# Camera_IR.net
KiCad netlist of a schematic drawn in EasyEDA
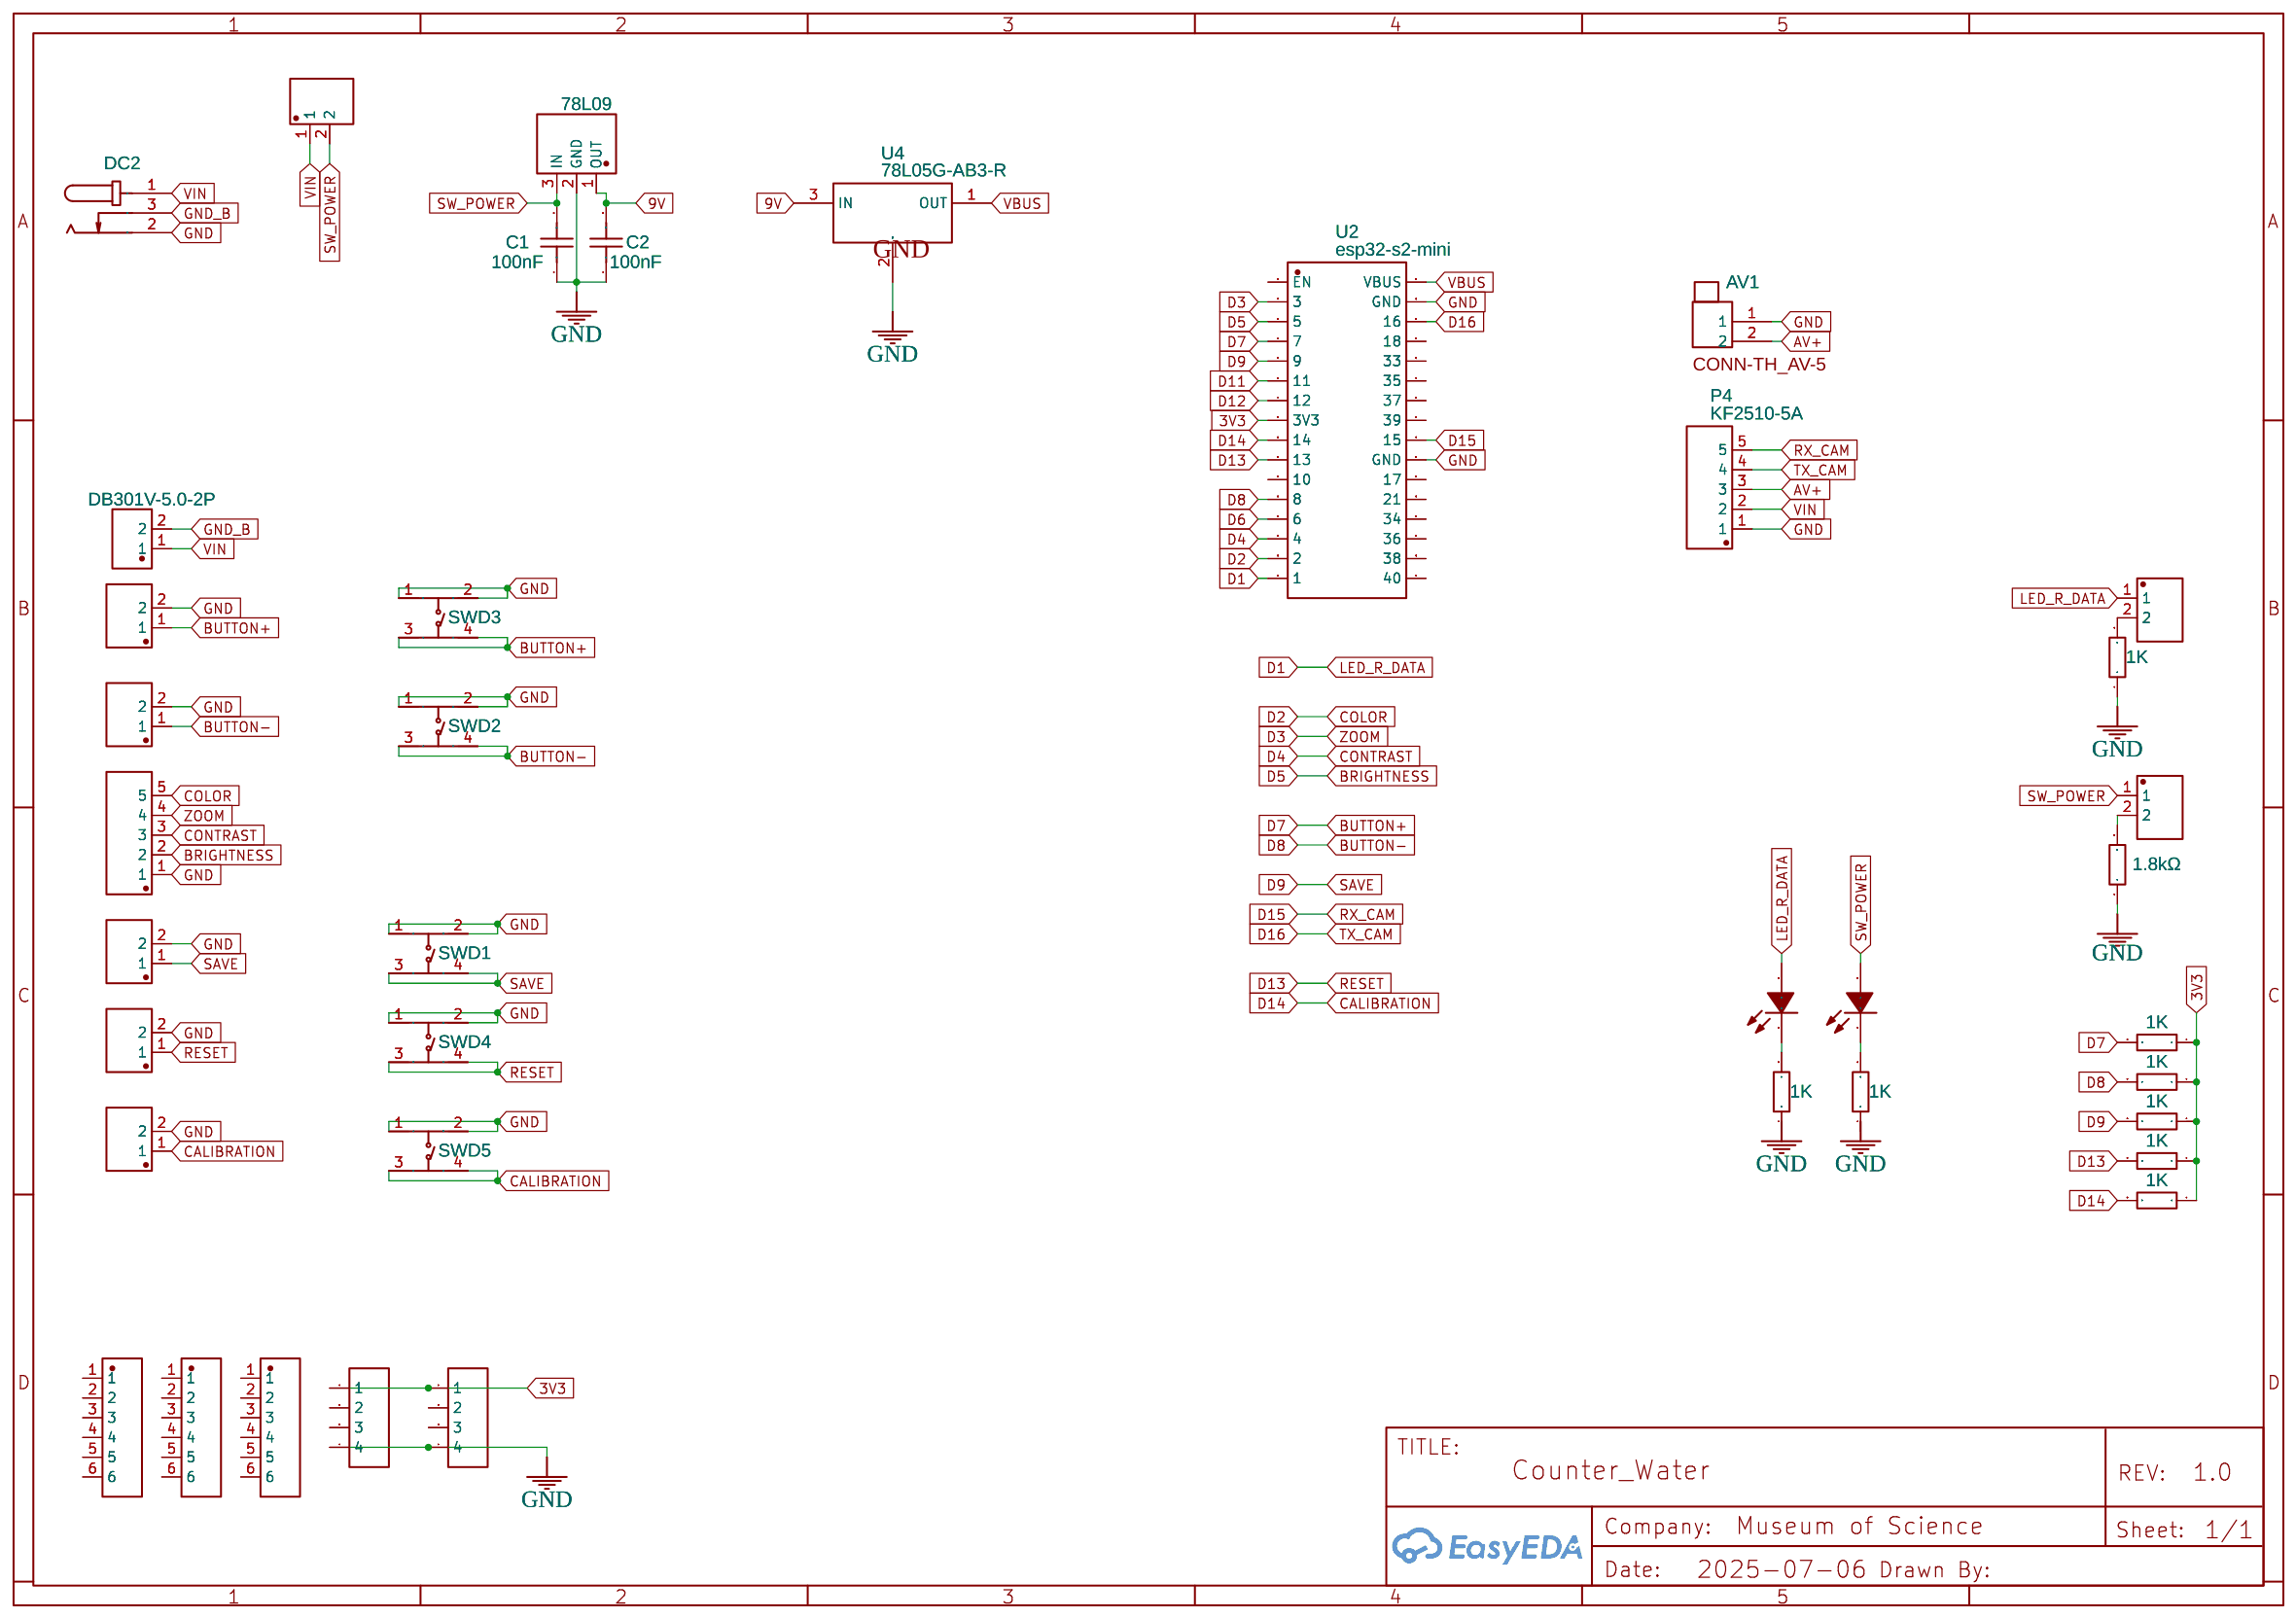
[diagram p0: schematic sheet]

(export (version "E")
  (design (tool "Eeschema 10.0.6"))
  (components
    (comp (ref "AV1")
      (value "AV-5")
      (fields (field (name "Manufacturer") "BOOMELE(博穆精密)"))
      (libsource (lib "") (part "AV-5"))
    )
    (comp (ref "C1")
      (value "100nF")
      (fields
        (field (name "Manufacturer Part") "CC0603KRX7R9BB104")
        (field (name "Manufacturer") "YAGEO(国巨)")
      )
      (libsource (lib "") (part "CC0603KRX7R9BB104"))
    )
    (comp (ref "C2")
      (value "100nF")
      (fields
        (field (name "Manufacturer Part") "CC0603KRX7R9BB104")
        (field (name "Manufacturer") "YAGEO(国巨)")
      )
      (libsource (lib "") (part "CC0603KRX7R9BB104"))
    )
    (comp (ref "D2")
      (value "LED_R_DATA")
      (fields (field (name "Manufacturer Part") "KF2510-2A") (field (name "Manufacturer") "BOOMELE"))
      (libsource (lib "") (part "KF2510-2A_2"))
    )
    (comp (ref "D7")
      (value "B+")
      (fields (field (name "Manufacturer Part") "KF2510-2A") (field (name "Manufacturer") "BOOMELE"))
      (libsource (lib "") (part "KF2510-2A"))
    )
    (comp (ref "D8")
      (value "B-")
      (fields (field (name "Manufacturer Part") "KF2510-2A") (field (name "Manufacturer") "BOOMELE"))
      (libsource (lib "") (part "KF2510-2A"))
    )
    (comp (ref "D9")
      (value "SAVE")
      (fields (field (name "Manufacturer Part") "KF2510-2A") (field (name "Manufacturer") "BOOMELE"))
      (libsource (lib "") (part "KF2510-2A"))
    )
    (comp (ref "D13")
      (value "RESET")
      (fields (field (name "Manufacturer Part") "KF2510-2A") (field (name "Manufacturer") "BOOMELE"))
      (libsource (lib "") (part "KF2510-2A"))
    )
    (comp (ref "D14")
      (value "FFC")
      (fields (field (name "Manufacturer Part") "KF2510-2A") (field (name "Manufacturer") "BOOMELE"))
      (libsource (lib "") (part "KF2510-2A"))
    )
    (comp (ref "DC2")
      (value "DC")
      (fields (field (name "Manufacturer Part") "DC005-2.0MM") (field (name "Manufacturer") "SOFNG"))
      (libsource (lib "") (part "DC005-2.0MM"))
    )
    (comp (ref "ERL1")
      (value "1K")
      (fields (field (name "Manufacturer Part") "0603WAF1001T5E") (field (name "Manufacturer") "UniOhm"))
      (libsource (lib "") (part "0603WAF1001T5E_1"))
    )
    (comp (ref "ERL2")
      (value "1K")
      (fields (field (name "Manufacturer Part") "0603WAF1001T5E") (field (name "Manufacturer") "UniOhm"))
      (libsource (lib "") (part "0603WAF1001T5E"))
    )
    (comp (ref "ERL4")
      (value "1K")
      (fields (field (name "Manufacturer Part") "0603WAF1001T5E") (field (name "Manufacturer") "UniOhm"))
      (libsource (lib "") (part "0603WAF1001T5E_1"))
    )
    (comp (ref "ERL5")
      (value "1K")
      (fields (field (name "Manufacturer Part") "0603WAF1001T5E") (field (name "Manufacturer") "UniOhm"))
      (libsource (lib "") (part "0603WAF1001T5E_1"))
    )
    (comp (ref "ERL6")
      (value "1K")
      (fields (field (name "Manufacturer Part") "0603WAF1001T5E") (field (name "Manufacturer") "UniOhm"))
      (libsource (lib "") (part "0603WAF1001T5E"))
    )
    (comp (ref "ERL9")
      (value "1K")
      (fields (field (name "Manufacturer Part") "0603WAF1001T5E") (field (name "Manufacturer") "UniOhm"))
      (libsource (lib "") (part "0603WAF1001T5E"))
    )
    (comp (ref "ERL11")
      (value "1K")
      (fields (field (name "Manufacturer Part") "0603WAF1001T5E") (field (name "Manufacturer") "UniOhm"))
      (libsource (lib "") (part "0603WAF1001T5E"))
    )
    (comp (ref "ERL12")
      (value "1K")
      (fields (field (name "Manufacturer Part") "0603WAF1001T5E") (field (name "Manufacturer") "UniOhm"))
      (libsource (lib "") (part "0603WAF1001T5E"))
    )
    (comp (ref "J6") (value "HDR-M-2.54_1x4") (libsource (lib "") (part "HDR-M-2.54_1x4")))
    (comp (ref "J7") (value "HDR-M-2.54_1x4") (libsource (lib "") (part "HDR-M-2.54_1x4")))
    (comp (ref "LED")
      (value "LED_POWER")
      (fields (field (name "Manufacturer Part") "KF2510-2A") (field (name "Manufacturer") "BOOMELE"))
      (libsource (lib "") (part "KF2510-2A_1"))
    )
    (comp (ref "LED4")
      (value "KT-0603R")
      (fields (field (name "Manufacturer") "KENTO"))
      (libsource (lib "") (part "KT-0603R"))
    )
    (comp (ref "LED5")
      (value "KT-0603R")
      (fields (field (name "Manufacturer") "KENTO"))
      (libsource (lib "") (part "KT-0603R"))
    )
    (comp (ref "P1")
      (value "KF2510-5A")
      (fields (field (name "Manufacturer Part") "2510-5A") (field (name "Manufacturer") "BOOMELE(博穆精密)"))
      (libsource (lib "") (part "KF2510-5A"))
    )
    (comp (ref "P2")
      (value "H6")
      (fields (field (name "Manufacturer Part") "2.54-1*6P母") (field (name "Manufacturer") "BOOMELE(博穆精密)"))
      (libsource (lib "") (part "Header-Female-2.54_1x6"))
    )
    (comp (ref "P3")
      (value "H6")
      (fields (field (name "Manufacturer Part") "2.54-1*6P母") (field (name "Manufacturer") "BOOMELE(博穆精密)"))
      (libsource (lib "") (part "Header-Female-2.54_1x6"))
    )
    (comp (ref "P4")
      (value "KF2510-5A")
      (fields (field (name "Manufacturer Part") "2510-5A") (field (name "Manufacturer") "BOOMELE(博穆精密)"))
      (libsource (lib "") (part "KF2510-5A"))
    )
    (comp (ref "P5")
      (value "H6")
      (fields (field (name "Manufacturer Part") "2.54-1*6P母") (field (name "Manufacturer") "BOOMELE(博穆精密)"))
      (libsource (lib "") (part "Header-Female-2.54_1x6"))
    )
    (comp (ref "R5")
      (value "1.8kΩ")
      (fields
        (field (name "Manufacturer Part") "0603WAF1801T5E")
        (field (name "Manufacturer") "UNI-ROYAL(厚声)")
      )
      (libsource (lib "") (part "0603WAF1801T5E"))
    )
    (comp (ref "SWD1")
      (value "TC-6610-7-160G")
      (fields (field (name "Manufacturer") "HCTL(华灿天禄)"))
      (libsource (lib "") (part "TC-6610-7-160G"))
    )
    (comp (ref "SWD2")
      (value "TC-6610-7-160G")
      (fields (field (name "Manufacturer") "HCTL(华灿天禄)"))
      (libsource (lib "") (part "TC-6610-7-160G"))
    )
    (comp (ref "SWD3")
      (value "TC-6610-7-160G")
      (fields (field (name "Manufacturer") "HCTL(华灿天禄)"))
      (libsource (lib "") (part "TC-6610-7-160G"))
    )
    (comp (ref "SWD4")
      (value "TC-6610-7-160G")
      (fields (field (name "Manufacturer") "HCTL(华灿天禄)"))
      (libsource (lib "") (part "TC-6610-7-160G"))
    )
    (comp (ref "SWD5")
      (value "TC-6610-7-160G")
      (fields (field (name "Manufacturer") "HCTL(华灿天禄)"))
      (libsource (lib "") (part "TC-6610-7-160G"))
    )
    (comp (ref "SW_P")
      (value "SW_P")
      (fields (field (name "Manufacturer Part") "KF2510-2A") (field (name "Manufacturer") "BOOMELE"))
      (libsource (lib "") (part "KF2510-2A_3"))
    )
    (comp (ref "U1")
      (value "78L09")
      (fields (field (name "Manufacturer") "CBI(创基)"))
      (libsource (lib "") (part "78L09U 78L09"))
    )
    (comp (ref "U2") (value "esp32-s2-mini") (libsource (lib "") (part "esp32-s2-mini")))
    (comp (ref "U3")
      (value "DB301V-5.0-2P")
      (fields
        (field (name "Manufacturer Part") "DB301V-5.0-2P-BU-S")
        (field (name "Manufacturer") "DORABO(地博电气)")
      )
      (libsource (lib "") (part "DB301V-5.0-2P"))
    )
    (comp (ref "U4")
      (value "78L05G-AB3-R")
      (fields (field (name "Manufacturer") "UTC(友顺)"))
      (libsource (lib "") (part "78L05G-AB3-R"))
    )
  )
  (nets
    (net (code "1") (name "3V3") (class "Default")
      (node (ref "ERL11") (pin "1") (pinfunction "1_1") (pintype "input"))
      (node (ref "ERL12") (pin "1") (pinfunction "1_1") (pintype "input"))
      (node (ref "ERL2") (pin "1") (pinfunction "1_1") (pintype "input"))
      (node (ref "ERL6") (pin "1") (pinfunction "1_1") (pintype "input"))
      (node (ref "ERL9") (pin "1") (pinfunction "1_1") (pintype "input"))
      (node (ref "J6") (pin "1") (pinfunction "1_1") (pintype "unspecified"))
      (node (ref "J7") (pin "1") (pinfunction "1_1") (pintype "unspecified"))
      (node (ref "U2") (pin "8") (pinfunction "3V3_8") (pintype "unspecified"))
    )
    (net (code "2") (name "9V") (class "Default")
      (node (ref "C2") (pin "2") (pinfunction "2_2") (pintype "unspecified"))
      (node (ref "U1") (pin "1") (pinfunction "OUT_1") (pintype "unspecified"))
      (node (ref "U4") (pin "3") (pinfunction "IN_3") (pintype "passive"))
    )
    (net (code "3") (name "AV+") (class "Default")
      (node (ref "AV1") (pin "2") (pinfunction "2_2") (pintype "unspecified"))
      (node (ref "P4") (pin "3") (pinfunction "3_3") (pintype "unspecified"))
    )
    (net (code "4") (name "BRIGHTNESS") (class "Default")
      (node (ref "P1") (pin "2") (pinfunction "2_2") (pintype "unspecified"))
      (node (ref "U2") (pin "3") (pinfunction "5_3") (pintype "unspecified"))
    )
    (net (code "5") (name "BUTTON+") (class "Default")
      (node (ref "D7") (pin "1") (pinfunction "1_1") (pintype "unspecified"))
      (node (ref "ERL6") (pin "2") (pinfunction "2_2") (pintype "input"))
      (node (ref "SWD3") (pin "3") (pinfunction "3_3") (pintype "unspecified"))
      (node (ref "SWD3") (pin "4") (pinfunction "4_4") (pintype "unspecified"))
      (node (ref "U2") (pin "4") (pinfunction "7_4") (pintype "unspecified"))
    )
    (net (code "6") (name "BUTTON-") (class "Default")
      (node (ref "D8") (pin "1") (pinfunction "1_1") (pintype "unspecified"))
      (node (ref "ERL11") (pin "2") (pinfunction "2_2") (pintype "input"))
      (node (ref "SWD2") (pin "3") (pinfunction "3_3") (pintype "unspecified"))
      (node (ref "SWD2") (pin "4") (pinfunction "4_4") (pintype "unspecified"))
      (node (ref "U2") (pin "12") (pinfunction "8_12") (pintype "unspecified"))
    )
    (net (code "7") (name "CALIBRATION") (class "Default")
      (node (ref "D14") (pin "1") (pinfunction "1_1") (pintype "unspecified"))
      (node (ref "ERL2") (pin "2") (pinfunction "2_2") (pintype "input"))
      (node (ref "SWD5") (pin "3") (pinfunction "3_3") (pintype "unspecified"))
      (node (ref "SWD5") (pin "4") (pinfunction "4_4") (pintype "unspecified"))
      (node (ref "U2") (pin "9") (pinfunction "14_9") (pintype "unspecified"))
    )
    (net (code "8") (name "COLOR") (class "Default")
      (node (ref "P1") (pin "5") (pinfunction "5_5") (pintype "unspecified"))
      (node (ref "U2") (pin "15") (pinfunction "2_15") (pintype "unspecified"))
    )
    (net (code "9") (name "CONTRAST") (class "Default")
      (node (ref "P1") (pin "3") (pinfunction "3_3") (pintype "unspecified"))
      (node (ref "U2") (pin "14") (pinfunction "4_14") (pintype "unspecified"))
    )
    (net (code "10") (name "D1") (class "Default")
      (node (ref "D2") (pin "1") (pinfunction "1_1") (pintype "unspecified"))
      (node (ref "LED5") (pin "2") (pinfunction "A_2") (pintype "unspecified"))
      (node (ref "U2") (pin "16") (pinfunction "1_16") (pintype "unspecified"))
    )
    (net (code "11") (name "D3") (class "Default")
      (node (ref "P1") (pin "4") (pinfunction "4_4") (pintype "unspecified"))
      (node (ref "U2") (pin "2") (pinfunction "3_2") (pintype "unspecified"))
    )
    (net (code "12") (name "D6") (class "Default")
      (node (ref "U2") (pin "13") (pinfunction "6_13") (pintype "unspecified"))
    )
    (net (code "13") (name "D9") (class "Default")
      (node (ref "D9") (pin "1") (pinfunction "1_1") (pintype "unspecified"))
      (node (ref "ERL9") (pin "2") (pinfunction "2_2") (pintype "input"))
      (node (ref "SWD1") (pin "3") (pinfunction "3_3") (pintype "unspecified"))
      (node (ref "SWD1") (pin "4") (pinfunction "4_4") (pintype "unspecified"))
      (node (ref "U2") (pin "5") (pinfunction "9_5") (pintype "unspecified"))
    )
    (net (code "14") (name "D11") (class "Default")
      (node (ref "U2") (pin "6") (pinfunction "11_6") (pintype "unspecified"))
    )
    (net (code "15") (name "D12") (class "Default")
      (node (ref "U2") (pin "7") (pinfunction "12_7") (pintype "unspecified"))
    )
    (net (code "16") (name "D13") (class "Default")
      (node (ref "D13") (pin "1") (pinfunction "1_1") (pintype "unspecified"))
      (node (ref "ERL12") (pin "2") (pinfunction "2_2") (pintype "input"))
      (node (ref "SWD4") (pin "3") (pinfunction "3_3") (pintype "unspecified"))
      (node (ref "SWD4") (pin "4") (pinfunction "4_4") (pintype "unspecified"))
      (node (ref "U2") (pin "10") (pinfunction "13_10") (pintype "unspecified"))
    )
    (net (code "17") (name "D15") (class "Default")
      (node (ref "P4") (pin "5") (pinfunction "5_5") (pintype "unspecified"))
      (node (ref "U2") (pin "24") (pinfunction "15_24") (pintype "unspecified"))
    )
    (net (code "18") (name "D16") (class "Default")
      (node (ref "P4") (pin "4") (pinfunction "4_4") (pintype "unspecified"))
      (node (ref "U2") (pin "30") (pinfunction "16_30") (pintype "unspecified"))
    )
    (net (code "19") (name "GND") (class "Default")
      (node (ref "AV1") (pin "1") (pinfunction "1_1") (pintype "unspecified"))
      (node (ref "C1") (pin "1") (pinfunction "1_1") (pintype "unspecified"))
      (node (ref "C2") (pin "1") (pinfunction "1_1") (pintype "unspecified"))
      (node (ref "D13") (pin "2") (pinfunction "2_2") (pintype "unspecified"))
      (node (ref "D14") (pin "2") (pinfunction "2_2") (pintype "unspecified"))
      (node (ref "D7") (pin "2") (pinfunction "2_2") (pintype "unspecified"))
      (node (ref "D8") (pin "2") (pinfunction "2_2") (pintype "unspecified"))
      (node (ref "D9") (pin "2") (pinfunction "2_2") (pintype "unspecified"))
      (node (ref "DC2") (pin "2") (pinfunction "2_2") (pintype "unspecified"))
      (node (ref "ERL1") (pin "1") (pinfunction "1_1") (pintype "input"))
      (node (ref "ERL4") (pin "1") (pinfunction "1_1") (pintype "input"))
      (node (ref "ERL5") (pin "1") (pinfunction "1_1") (pintype "input"))
      (node (ref "J6") (pin "4") (pinfunction "4_4") (pintype "unspecified"))
      (node (ref "J7") (pin "4") (pinfunction "4_4") (pintype "unspecified"))
      (node (ref "P1") (pin "1") (pinfunction "1_1") (pintype "unspecified"))
      (node (ref "P4") (pin "1") (pinfunction "1_1") (pintype "unspecified"))
      (node (ref "R5") (pin "1") (pinfunction "1_1") (pintype "input"))
      (node (ref "SWD1") (pin "1") (pinfunction "1_1") (pintype "unspecified"))
      (node (ref "SWD1") (pin "2") (pinfunction "2_2") (pintype "unspecified"))
      (node (ref "SWD2") (pin "1") (pinfunction "1_1") (pintype "unspecified"))
      (node (ref "SWD2") (pin "2") (pinfunction "2_2") (pintype "unspecified"))
      (node (ref "SWD3") (pin "1") (pinfunction "1_1") (pintype "unspecified"))
      (node (ref "SWD3") (pin "2") (pinfunction "2_2") (pintype "unspecified"))
      (node (ref "SWD4") (pin "1") (pinfunction "1_1") (pintype "unspecified"))
      (node (ref "SWD4") (pin "2") (pinfunction "2_2") (pintype "unspecified"))
      (node (ref "SWD5") (pin "1") (pinfunction "1_1") (pintype "unspecified"))
      (node (ref "SWD5") (pin "2") (pinfunction "2_2") (pintype "unspecified"))
      (node (ref "U1") (pin "2") (pinfunction "GND_2") (pintype "unspecified"))
      (node (ref "U2") (pin "23") (pinfunction "GND_23") (pintype "unspecified"))
      (node (ref "U2") (pin "31") (pinfunction "GND_31") (pintype "unspecified"))
      (node (ref "U4") (pin "2") (pinfunction "GND_2") (pintype "passive"))
    )
    (net (code "20") (name "GND_B") (class "Default")
      (node (ref "DC2") (pin "3") (pinfunction "3_3") (pintype "unspecified"))
      (node (ref "U3") (pin "2") (pinfunction "2_2") (pintype "unspecified"))
    )
    (net (code "21") (name "Net-(D2-Pad2)") (class "Default")
      (node (ref "D2") (pin "2") (pinfunction "2_2") (pintype "unspecified"))
      (node (ref "ERL5") (pin "2") (pinfunction "2_2") (pintype "input"))
    )
    (net (code "22") (name "Net-(LED-Pad2)") (class "Default")
      (node (ref "LED") (pin "2") (pinfunction "2_2") (pintype "unspecified"))
      (node (ref "R5") (pin "2") (pinfunction "2_2") (pintype "input"))
    )
    (net (code "23") (name "Net-(LED4-K)") (class "Default")
      (node (ref "ERL4") (pin "2") (pinfunction "2_2") (pintype "input"))
      (node (ref "LED4") (pin "1") (pinfunction "K_1") (pintype "unspecified"))
    )
    (net (code "24") (name "Net-(LED5-K)") (class "Default")
      (node (ref "ERL1") (pin "2") (pinfunction "2_2") (pintype "input"))
      (node (ref "LED5") (pin "1") (pinfunction "K_1") (pintype "unspecified"))
    )
    (net (code "25") (name "SW_POWER") (class "Default")
      (node (ref "C1") (pin "2") (pinfunction "2_2") (pintype "unspecified"))
      (node (ref "LED") (pin "1") (pinfunction "1_1") (pintype "unspecified"))
      (node (ref "LED4") (pin "2") (pinfunction "A_2") (pintype "unspecified"))
      (node (ref "SW_P") (pin "2") (pinfunction "2_2") (pintype "unspecified"))
      (node (ref "U1") (pin "3") (pinfunction "IN_3") (pintype "unspecified"))
    )
    (net (code "26") (name "VBUS") (class "Default")
      (node (ref "U2") (pin "32") (pinfunction "VBUS_32") (pintype "unspecified"))
      (node (ref "U4") (pin "1") (pinfunction "OUT_1") (pintype "passive"))
    )
    (net (code "27") (name "VIN") (class "Default")
      (node (ref "DC2") (pin "1") (pinfunction "1_1") (pintype "unspecified"))
      (node (ref "P4") (pin "2") (pinfunction "2_2") (pintype "unspecified"))
      (node (ref "SW_P") (pin "1") (pinfunction "1_1") (pintype "unspecified"))
      (node (ref "U3") (pin "1") (pinfunction "1_1") (pintype "unspecified"))
    )
    (net (code "28") (name "unconnected-(J6-Pad2)") (class "Default")
      (node (ref "J6") (pin "2") (pinfunction "2_2") (pintype "unspecified"))
    )
    (net (code "29") (name "unconnected-(J6-Pad3)") (class "Default")
      (node (ref "J6") (pin "3") (pinfunction "3_3") (pintype "unspecified"))
    )
    (net (code "30") (name "unconnected-(J7-Pad2)") (class "Default")
      (node (ref "J7") (pin "2") (pinfunction "2_2") (pintype "unspecified"))
    )
    (net (code "31") (name "unconnected-(J7-Pad3)") (class "Default")
      (node (ref "J7") (pin "3") (pinfunction "3_3") (pintype "unspecified"))
    )
    (net (code "32") (name "unconnected-(P2-Pad1)") (class "Default")
      (node (ref "P2") (pin "1") (pinfunction "1_1") (pintype "unspecified"))
    )
    (net (code "33") (name "unconnected-(P2-Pad2)") (class "Default")
      (node (ref "P2") (pin "2") (pinfunction "2_2") (pintype "unspecified"))
    )
    (net (code "34") (name "unconnected-(P2-Pad3)") (class "Default")
      (node (ref "P2") (pin "3") (pinfunction "3_3") (pintype "unspecified"))
    )
    (net (code "35") (name "unconnected-(P2-Pad4)") (class "Default")
      (node (ref "P2") (pin "4") (pinfunction "4_4") (pintype "unspecified"))
    )
    (net (code "36") (name "unconnected-(P2-Pad5)") (class "Default")
      (node (ref "P2") (pin "5") (pinfunction "5_5") (pintype "unspecified"))
    )
    (net (code "37") (name "unconnected-(P2-Pad6)") (class "Default")
      (node (ref "P2") (pin "6") (pinfunction "6_6") (pintype "unspecified"))
    )
    (net (code "38") (name "unconnected-(P3-Pad1)") (class "Default")
      (node (ref "P3") (pin "1") (pinfunction "1_1") (pintype "unspecified"))
    )
    (net (code "39") (name "unconnected-(P3-Pad2)") (class "Default")
      (node (ref "P3") (pin "2") (pinfunction "2_2") (pintype "unspecified"))
    )
    (net (code "40") (name "unconnected-(P3-Pad3)") (class "Default")
      (node (ref "P3") (pin "3") (pinfunction "3_3") (pintype "unspecified"))
    )
    (net (code "41") (name "unconnected-(P3-Pad4)") (class "Default")
      (node (ref "P3") (pin "4") (pinfunction "4_4") (pintype "unspecified"))
    )
    (net (code "42") (name "unconnected-(P3-Pad5)") (class "Default")
      (node (ref "P3") (pin "5") (pinfunction "5_5") (pintype "unspecified"))
    )
    (net (code "43") (name "unconnected-(P3-Pad6)") (class "Default")
      (node (ref "P3") (pin "6") (pinfunction "6_6") (pintype "unspecified"))
    )
    (net (code "44") (name "unconnected-(P5-Pad1)") (class "Default")
      (node (ref "P5") (pin "1") (pinfunction "1_1") (pintype "unspecified"))
    )
    (net (code "45") (name "unconnected-(P5-Pad2)") (class "Default")
      (node (ref "P5") (pin "2") (pinfunction "2_2") (pintype "unspecified"))
    )
    (net (code "46") (name "unconnected-(P5-Pad3)") (class "Default")
      (node (ref "P5") (pin "3") (pinfunction "3_3") (pintype "unspecified"))
    )
    (net (code "47") (name "unconnected-(P5-Pad4)") (class "Default")
      (node (ref "P5") (pin "4") (pinfunction "4_4") (pintype "unspecified"))
    )
    (net (code "48") (name "unconnected-(P5-Pad5)") (class "Default")
      (node (ref "P5") (pin "5") (pinfunction "5_5") (pintype "unspecified"))
    )
    (net (code "49") (name "unconnected-(P5-Pad6)") (class "Default")
      (node (ref "P5") (pin "6") (pinfunction "6_6") (pintype "unspecified"))
    )
    (net (code "50") (name "unconnected-(U2-10-Pad11)") (class "Default")
      (node (ref "U2") (pin "11") (pinfunction "10_11") (pintype "unspecified"))
    )
    (net (code "51") (name "unconnected-(U2-17-Pad22)") (class "Default")
      (node (ref "U2") (pin "22") (pinfunction "17_22") (pintype "unspecified"))
    )
    (net (code "52") (name "unconnected-(U2-18-Pad29)") (class "Default")
      (node (ref "U2") (pin "29") (pinfunction "18_29") (pintype "unspecified"))
    )
    (net (code "53") (name "unconnected-(U2-33-Pad28)") (class "Default")
      (node (ref "U2") (pin "28") (pinfunction "33_28") (pintype "unspecified"))
    )
    (net (code "54") (name "unconnected-(U2-34-Pad20)") (class "Default")
      (node (ref "U2") (pin "20") (pinfunction "34_20") (pintype "unspecified"))
    )
    (net (code "55") (name "unconnected-(U2-35-Pad27)") (class "Default")
      (node (ref "U2") (pin "27") (pinfunction "35_27") (pintype "unspecified"))
    )
    (net (code "56") (name "unconnected-(U2-36-Pad19)") (class "Default")
      (node (ref "U2") (pin "19") (pinfunction "36_19") (pintype "unspecified"))
    )
    (net (code "57") (name "unconnected-(U2-37-Pad26)") (class "Default")
      (node (ref "U2") (pin "26") (pinfunction "37_26") (pintype "unspecified"))
    )
    (net (code "58") (name "unconnected-(U2-38-Pad18)") (class "Default")
      (node (ref "U2") (pin "18") (pinfunction "38_18") (pintype "unspecified"))
    )
    (net (code "59") (name "unconnected-(U2-39-Pad25)") (class "Default")
      (node (ref "U2") (pin "25") (pinfunction "39_25") (pintype "unspecified"))
    )
    (net (code "60") (name "unconnected-(U2-40-Pad17)") (class "Default")
      (node (ref "U2") (pin "17") (pinfunction "40_17") (pintype "unspecified"))
    )
    (net (code "61") (name "unconnected-(U2-EN-Pad1)") (class "Default")
      (node (ref "U2") (pin "1") (pinfunction "EN_1") (pintype "unspecified"))
    )
    (net (code "62") (name "unconnected-(U2-Pad21)") (class "Default")
      (node (ref "U2") (pin "21") (pinfunction "21_21") (pintype "unspecified"))
    )
  )
)
